# PCB_V7.net
KiCad netlist of a schematic drawn in EAGLE
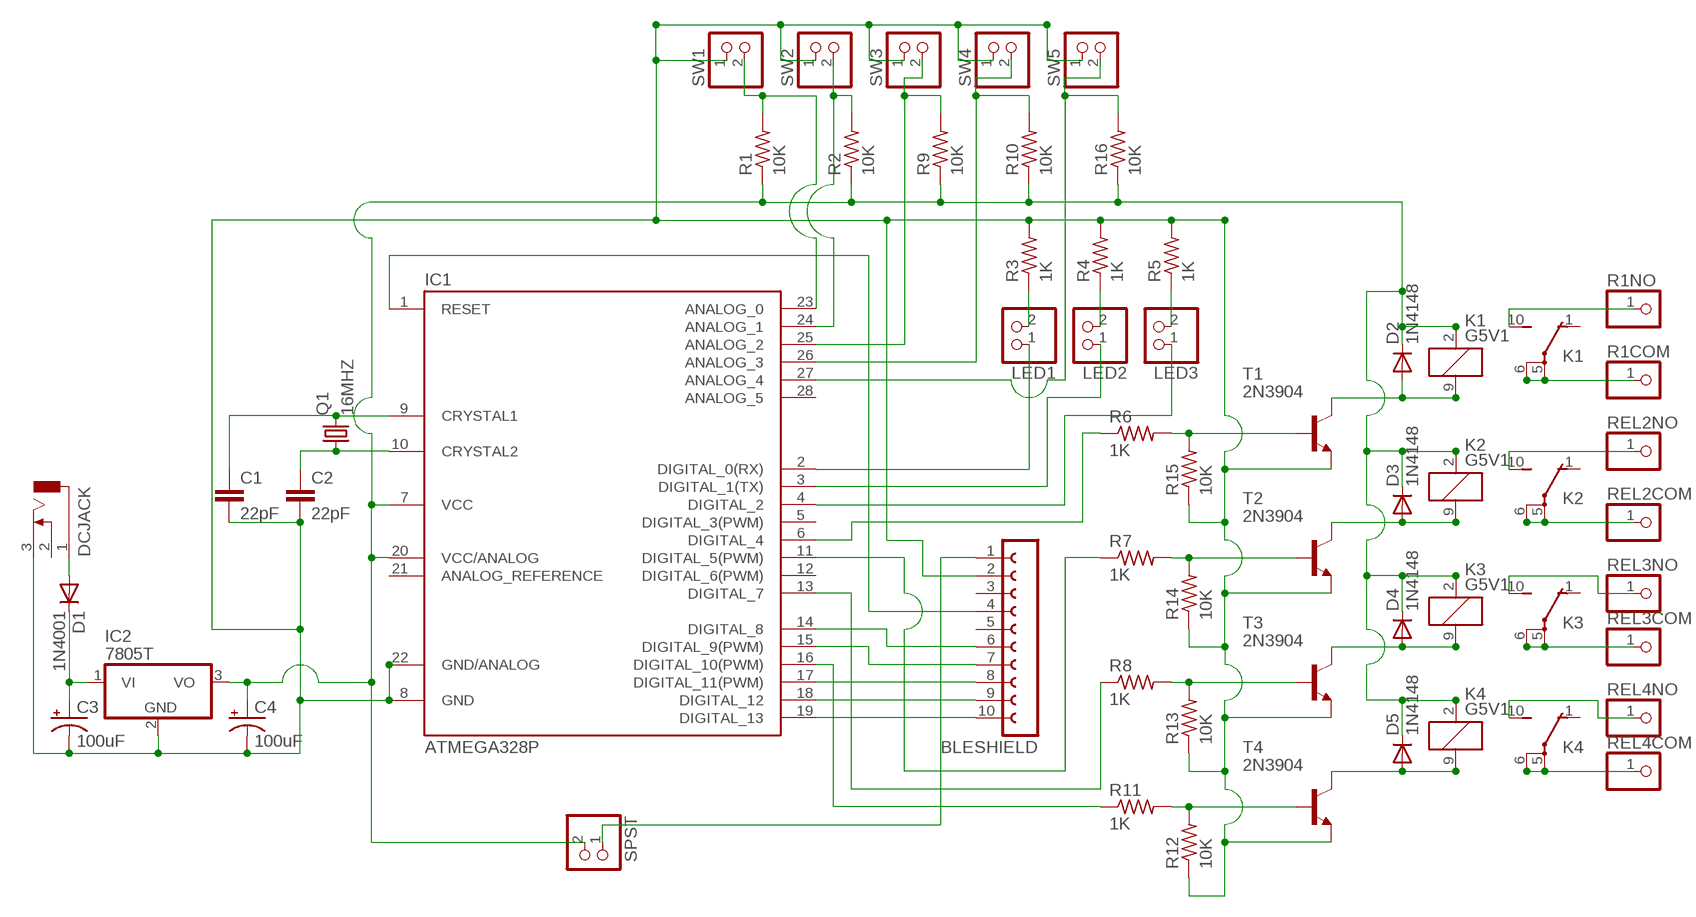
[diagram p0: schematic, sheet 1]

(export (version "E")
  (design (tool "Eeschema 10.0.6"))
  (components
    (comp (ref "BLESHIELD")
      (value "FE10-1")
      (footprint "eagle-import:FE10")
      (libsource (lib "eagle-import") (part "FE10-1"))
    )
    (comp (ref "C1")
      (value "22pF")
      (footprint "eagle-import:C025-030X050")
      (libsource (lib "eagle-import") (part "C-EU025-030X050"))
    )
    (comp (ref "C2")
      (value "22pF")
      (footprint "eagle-import:C025-030X050")
      (libsource (lib "eagle-import") (part "C-EU025-030X050"))
    )
    (comp (ref "C3")
      (value "100uF")
      (footprint "eagle-import:E2,5-6")
      (libsource (lib "eagle-import") (part "CPOL-USE2.5-6"))
    )
    (comp (ref "C4")
      (value "100uF")
      (footprint "eagle-import:E2,5-6")
      (libsource (lib "eagle-import") (part "CPOL-USE2.5-6"))
    )
    (comp (ref "D1")
      (value "1N4001")
      (footprint "eagle-import:DO41-10")
      (libsource (lib "eagle-import") (part "1N4004"))
    )
    (comp (ref "D2")
      (value "1N4148")
      (footprint "eagle-import:DO35-7")
      (libsource (lib "eagle-import") (part "1N4148DO35-7"))
    )
    (comp (ref "D3")
      (value "1N4148")
      (footprint "eagle-import:DO35-7")
      (libsource (lib "eagle-import") (part "1N4148DO35-7"))
    )
    (comp (ref "D4")
      (value "1N4148")
      (footprint "eagle-import:DO35-7")
      (libsource (lib "eagle-import") (part "1N4148DO35-7"))
    )
    (comp (ref "D5")
      (value "1N4148")
      (footprint "eagle-import:DO35-7")
      (libsource (lib "eagle-import") (part "1N4148DO35-7"))
    )
    (comp (ref "DCJACK")
      (value "DCJ0202")
      (footprint "eagle-import:DCJ0202")
      (libsource (lib "eagle-import") (part "DCJ0202"))
    )
    (comp (ref "IC1")
      (value "ATMEGA328P")
      (footprint "eagle-import:DIL28-3")
      (libsource (lib "eagle-import") (part "ATMEGA168-PU"))
    )
    (comp (ref "IC2")
      (value "7805T")
      (footprint "eagle-import:TO220H")
      (libsource (lib "eagle-import") (part "78T05"))
    )
    (comp (ref "K1")
      (value "G5V1")
      (footprint "eagle-import:G5V1")
      (fields (field (name "MPN") "G5V-1-DC24"))
      (libsource (lib "eagle-import") (part "G5V1"))
    )
    (comp (ref "K2")
      (value "G5V1")
      (footprint "eagle-import:G5V1")
      (fields (field (name "MPN") "G5V-1-DC24"))
      (libsource (lib "eagle-import") (part "G5V1"))
    )
    (comp (ref "K3")
      (value "G5V1")
      (footprint "eagle-import:G5V1")
      (fields (field (name "MPN") "G5V-1-DC24"))
      (libsource (lib "eagle-import") (part "G5V1"))
    )
    (comp (ref "K4")
      (value "G5V1")
      (footprint "eagle-import:G5V1")
      (fields (field (name "MPN") "G5V-1-DC24"))
      (libsource (lib "eagle-import") (part "G5V1"))
    )
    (comp (ref "LED1")
      (value "PINHD-1X2")
      (footprint "eagle-import:1X02")
      (libsource (lib "eagle-import") (part "PINHD-1X2"))
    )
    (comp (ref "LED2")
      (value "PINHD-1X2")
      (footprint "eagle-import:1X02")
      (libsource (lib "eagle-import") (part "PINHD-1X2"))
    )
    (comp (ref "LED3")
      (value "PINHD-1X2")
      (footprint "eagle-import:1X02")
      (libsource (lib "eagle-import") (part "PINHD-1X2"))
    )
    (comp (ref "Q1")
      (value "16MHZ")
      (footprint "eagle-import:HC49_S")
      (libsource (lib "eagle-import") (part "CRYSTALHC49S"))
    )
    (comp (ref "R1")
      (value "10K")
      (footprint "eagle-import:0204_5")
      (libsource (lib "eagle-import") (part "R-US_0204/5"))
    )
    (comp (ref "R1COM")
      (value "PINHD-1X1")
      (footprint "eagle-import:1X01")
      (libsource (lib "eagle-import") (part "PINHD-1X1"))
    )
    (comp (ref "R1NO")
      (value "PINHD-1X1")
      (footprint "eagle-import:1X01")
      (libsource (lib "eagle-import") (part "PINHD-1X1"))
    )
    (comp (ref "R2")
      (value "10K")
      (footprint "eagle-import:0204_5")
      (libsource (lib "eagle-import") (part "R-US_0204/5"))
    )
    (comp (ref "R3")
      (value "1K")
      (footprint "eagle-import:0204_5")
      (libsource (lib "eagle-import") (part "R-US_0204/5"))
    )
    (comp (ref "R4")
      (value "1K")
      (footprint "eagle-import:0204_5")
      (libsource (lib "eagle-import") (part "R-US_0204/5"))
    )
    (comp (ref "R5")
      (value "1K")
      (footprint "eagle-import:0204_5")
      (libsource (lib "eagle-import") (part "R-US_0204/5"))
    )
    (comp (ref "R6")
      (value "1K")
      (footprint "eagle-import:0204_5")
      (libsource (lib "eagle-import") (part "R-US_0204/5"))
    )
    (comp (ref "R7")
      (value "1K")
      (footprint "eagle-import:0204_5")
      (libsource (lib "eagle-import") (part "R-US_0204/5"))
    )
    (comp (ref "R8")
      (value "1K")
      (footprint "eagle-import:0204_5")
      (libsource (lib "eagle-import") (part "R-US_0204/5"))
    )
    (comp (ref "R9")
      (value "10K")
      (footprint "eagle-import:0204_5")
      (libsource (lib "eagle-import") (part "R-US_0204/5"))
    )
    (comp (ref "R10")
      (value "10K")
      (footprint "eagle-import:0204_5")
      (libsource (lib "eagle-import") (part "R-US_0204/5"))
    )
    (comp (ref "R11")
      (value "1K")
      (footprint "eagle-import:0204_5")
      (libsource (lib "eagle-import") (part "R-US_0204/5"))
    )
    (comp (ref "R12")
      (value "10K")
      (footprint "eagle-import:0204_5")
      (libsource (lib "eagle-import") (part "R-US_0204/5"))
    )
    (comp (ref "R13")
      (value "10K")
      (footprint "eagle-import:0204_5")
      (libsource (lib "eagle-import") (part "R-US_0204/5"))
    )
    (comp (ref "R14")
      (value "10K")
      (footprint "eagle-import:0204_5")
      (libsource (lib "eagle-import") (part "R-US_0204/5"))
    )
    (comp (ref "R15")
      (value "10K")
      (footprint "eagle-import:0204_5")
      (libsource (lib "eagle-import") (part "R-US_0204/5"))
    )
    (comp (ref "R16")
      (value "10K")
      (footprint "eagle-import:0204_5")
      (libsource (lib "eagle-import") (part "R-US_0204/5"))
    )
    (comp (ref "REL2COM")
      (value "PINHD-1X1")
      (footprint "eagle-import:1X01")
      (libsource (lib "eagle-import") (part "PINHD-1X1"))
    )
    (comp (ref "REL2NO")
      (value "PINHD-1X1")
      (footprint "eagle-import:1X01")
      (libsource (lib "eagle-import") (part "PINHD-1X1"))
    )
    (comp (ref "REL3COM")
      (value "PINHD-1X1")
      (footprint "eagle-import:1X01")
      (libsource (lib "eagle-import") (part "PINHD-1X1"))
    )
    (comp (ref "REL3NO")
      (value "PINHD-1X1")
      (footprint "eagle-import:1X01")
      (libsource (lib "eagle-import") (part "PINHD-1X1"))
    )
    (comp (ref "REL4COM")
      (value "PINHD-1X1")
      (footprint "eagle-import:1X01")
      (libsource (lib "eagle-import") (part "PINHD-1X1"))
    )
    (comp (ref "REL4NO")
      (value "PINHD-1X1")
      (footprint "eagle-import:1X01")
      (libsource (lib "eagle-import") (part "PINHD-1X1"))
    )
    (comp (ref "SPST")
      (value "PINHD-1X2")
      (footprint "eagle-import:1X02")
      (libsource (lib "eagle-import") (part "PINHD-1X2"))
    )
    (comp (ref "SW1")
      (value "PINHD-1X2")
      (footprint "eagle-import:1X02")
      (libsource (lib "eagle-import") (part "PINHD-1X2"))
    )
    (comp (ref "SW2")
      (value "PINHD-1X2")
      (footprint "eagle-import:1X02")
      (libsource (lib "eagle-import") (part "PINHD-1X2"))
    )
    (comp (ref "SW3")
      (value "PINHD-1X2")
      (footprint "eagle-import:1X02")
      (libsource (lib "eagle-import") (part "PINHD-1X2"))
    )
    (comp (ref "SW4")
      (value "PINHD-1X2")
      (footprint "eagle-import:1X02")
      (libsource (lib "eagle-import") (part "PINHD-1X2"))
    )
    (comp (ref "SW5")
      (value "PINHD-1X2")
      (footprint "eagle-import:1X02")
      (libsource (lib "eagle-import") (part "PINHD-1X2"))
    )
    (comp (ref "T1")
      (value "2N3904")
      (footprint "eagle-import:TO92")
      (libsource (lib "eagle-import") (part "2N3904"))
    )
    (comp (ref "T2")
      (value "2N3904")
      (footprint "eagle-import:TO92")
      (libsource (lib "eagle-import") (part "2N3904"))
    )
    (comp (ref "T3")
      (value "2N3904")
      (footprint "eagle-import:TO92")
      (libsource (lib "eagle-import") (part "2N3904"))
    )
    (comp (ref "T4")
      (value "2N3904")
      (footprint "eagle-import:TO92")
      (libsource (lib "eagle-import") (part "2N3904"))
    )
  )
  (nets
    (net (code "1") (name "Net-(BLESHIELD-Pad1)") (class "Default")
      (node (ref "BLESHIELD") (pin "1") (pinfunction "1_1") (pintype "passive"))
      (node (ref "SPST") (pin "1") (pinfunction "1_1") (pintype "passive"))
    )
    (net (code "2") (name "Net-(D1-PadA)") (class "Default")
      (node (ref "D1") (pin "A") (pinfunction "A_A") (pintype "passive"))
      (node (ref "DCJACK") (pin "1") (pinfunction "1_1") (pintype "passive"))
    )
    (net (code "3") (name "Net-(IC1-ANALOG_0)") (class "Default")
      (node (ref "IC1") (pin "23") (pinfunction "ANALOG_0_23") (pintype "bidirectional"))
      (node (ref "R1") (pin "2") (pinfunction "2_2") (pintype "passive"))
      (node (ref "SW1") (pin "2") (pinfunction "2_2") (pintype "passive"))
    )
    (net (code "4") (name "Net-(IC1-ANALOG_1)") (class "Default")
      (node (ref "IC1") (pin "24") (pinfunction "ANALOG_1_24") (pintype "bidirectional"))
      (node (ref "R2") (pin "2") (pinfunction "2_2") (pintype "passive"))
      (node (ref "SW2") (pin "2") (pinfunction "2_2") (pintype "passive"))
    )
    (net (code "5") (name "Net-(IC1-ANALOG_2)") (class "Default")
      (node (ref "IC1") (pin "25") (pinfunction "ANALOG_2_25") (pintype "bidirectional"))
      (node (ref "R9") (pin "2") (pinfunction "2_2") (pintype "passive"))
      (node (ref "SW3") (pin "2") (pinfunction "2_2") (pintype "passive"))
    )
    (net (code "6") (name "Net-(IC1-ANALOG_3)") (class "Default")
      (node (ref "IC1") (pin "26") (pinfunction "ANALOG_3_26") (pintype "bidirectional"))
      (node (ref "R10") (pin "2") (pinfunction "2_2") (pintype "passive"))
      (node (ref "SW4") (pin "2") (pinfunction "2_2") (pintype "passive"))
    )
    (net (code "7") (name "Net-(IC1-ANALOG_4)") (class "Default")
      (node (ref "IC1") (pin "27") (pinfunction "ANALOG_4_27") (pintype "bidirectional"))
      (node (ref "R16") (pin "2") (pinfunction "2_2") (pintype "passive"))
      (node (ref "SW5") (pin "2") (pinfunction "2_2") (pintype "passive"))
    )
    (net (code "8") (name "Net-(IC1-CRYSTAL1)") (class "Default")
      (node (ref "C1") (pin "1") (pinfunction "1_1") (pintype "passive"))
      (node (ref "IC1") (pin "9") (pinfunction "CRYSTAL1_9") (pintype "bidirectional"))
      (node (ref "Q1") (pin "2") (pinfunction "2_2") (pintype "passive"))
    )
    (net (code "9") (name "Net-(IC1-CRYSTAL2)") (class "Default")
      (node (ref "C2") (pin "1") (pinfunction "1_1") (pintype "passive"))
      (node (ref "IC1") (pin "10") (pinfunction "CRYSTAL2_10") (pintype "bidirectional"))
      (node (ref "Q1") (pin "1") (pinfunction "1_1") (pintype "passive"))
    )
    (net (code "10") (name "Net-(IC1-DIGITAL_0(RX))") (class "Default")
      (node (ref "IC1") (pin "2") (pinfunction "DIGITAL_0(RX)_2") (pintype "bidirectional"))
      (node (ref "LED1") (pin "1") (pinfunction "1_1") (pintype "passive"))
    )
    (net (code "11") (name "Net-(IC1-DIGITAL_1(TX))") (class "Default")
      (node (ref "IC1") (pin "3") (pinfunction "DIGITAL_1(TX)_3") (pintype "bidirectional"))
      (node (ref "LED2") (pin "1") (pinfunction "1_1") (pintype "passive"))
    )
    (net (code "12") (name "Net-(IC1-DIGITAL_2)") (class "Default")
      (node (ref "IC1") (pin "4") (pinfunction "DIGITAL_2_4") (pintype "bidirectional"))
      (node (ref "LED3") (pin "1") (pinfunction "1_1") (pintype "passive"))
    )
    (net (code "13") (name "Net-(IC1-DIGITAL_4)") (class "Default")
      (node (ref "IC1") (pin "6") (pinfunction "DIGITAL_4_6") (pintype "bidirectional"))
      (node (ref "R6") (pin "1") (pinfunction "1_1") (pintype "passive"))
    )
    (net (code "14") (name "Net-(IC1-DIGITAL_5(PWM))") (class "Default")
      (node (ref "IC1") (pin "11") (pinfunction "DIGITAL_5(PWM)_11") (pintype "bidirectional"))
      (node (ref "R7") (pin "1") (pinfunction "1_1") (pintype "passive"))
    )
    (net (code "15") (name "Net-(IC1-DIGITAL_7)") (class "Default")
      (node (ref "IC1") (pin "13") (pinfunction "DIGITAL_7_13") (pintype "bidirectional"))
      (node (ref "R8") (pin "1") (pinfunction "1_1") (pintype "passive"))
    )
    (net (code "16") (name "Net-(IC1-DIGITAL_8)") (class "Default")
      (node (ref "BLESHIELD") (pin "6") (pinfunction "6_6") (pintype "passive"))
      (node (ref "IC1") (pin "14") (pinfunction "DIGITAL_8_14") (pintype "bidirectional"))
    )
    (net (code "17") (name "Net-(IC1-DIGITAL_9(PWM))") (class "Default")
      (node (ref "BLESHIELD") (pin "7") (pinfunction "7_7") (pintype "passive"))
      (node (ref "IC1") (pin "15") (pinfunction "DIGITAL_9(PWM)_15") (pintype "bidirectional"))
    )
    (net (code "18") (name "Net-(IC1-DIGITAL_10(PWM))") (class "Default")
      (node (ref "IC1") (pin "16") (pinfunction "DIGITAL_10(PWM)_16") (pintype "bidirectional"))
      (node (ref "R11") (pin "1") (pinfunction "1_1") (pintype "passive"))
    )
    (net (code "19") (name "Net-(IC1-DIGITAL_11(PWM))") (class "Default")
      (node (ref "BLESHIELD") (pin "8") (pinfunction "8_8") (pintype "passive"))
      (node (ref "IC1") (pin "17") (pinfunction "DIGITAL_11(PWM)_17") (pintype "bidirectional"))
    )
    (net (code "20") (name "Net-(IC1-DIGITAL_12)") (class "Default")
      (node (ref "BLESHIELD") (pin "9") (pinfunction "9_9") (pintype "passive"))
      (node (ref "IC1") (pin "18") (pinfunction "DIGITAL_12_18") (pintype "bidirectional"))
    )
    (net (code "21") (name "Net-(IC1-DIGITAL_13)") (class "Default")
      (node (ref "BLESHIELD") (pin "10") (pinfunction "10_10") (pintype "passive"))
      (node (ref "IC1") (pin "19") (pinfunction "DIGITAL_13_19") (pintype "bidirectional"))
    )
    (net (code "22") (name "Net-(IC1-GND)") (class "Default")
      (node (ref "BLESHIELD") (pin "2") (pinfunction "2_2") (pintype "passive"))
      (node (ref "C1") (pin "2") (pinfunction "2_2") (pintype "passive"))
      (node (ref "C2") (pin "2") (pinfunction "2_2") (pintype "passive"))
      (node (ref "C3") (pin "-") (pinfunction "-_-") (pintype "passive"))
      (node (ref "C4") (pin "-") (pinfunction "-_-") (pintype "passive"))
      (node (ref "DCJACK") (pin "3") (pinfunction "3_3") (pintype "passive"))
      (node (ref "IC1") (pin "22") (pinfunction "GND/ANALOG_22") (pintype "power_in"))
      (node (ref "IC1") (pin "8") (pinfunction "GND_8") (pintype "power_in"))
      (node (ref "IC2") (pin "2") (pinfunction "GND_2") (pintype "passive"))
      (node (ref "R12") (pin "1") (pinfunction "1_1") (pintype "passive"))
      (node (ref "R13") (pin "1") (pinfunction "1_1") (pintype "passive"))
      (node (ref "R14") (pin "1") (pinfunction "1_1") (pintype "passive"))
      (node (ref "R15") (pin "1") (pinfunction "1_1") (pintype "passive"))
      (node (ref "R3") (pin "2") (pinfunction "2_2") (pintype "passive"))
      (node (ref "R4") (pin "2") (pinfunction "2_2") (pintype "passive"))
      (node (ref "R5") (pin "2") (pinfunction "2_2") (pintype "passive"))
      (node (ref "SW1") (pin "1") (pinfunction "1_1") (pintype "passive"))
      (node (ref "SW2") (pin "1") (pinfunction "1_1") (pintype "passive"))
      (node (ref "SW3") (pin "1") (pinfunction "1_1") (pintype "passive"))
      (node (ref "SW4") (pin "1") (pinfunction "1_1") (pintype "passive"))
      (node (ref "SW5") (pin "1") (pinfunction "1_1") (pintype "passive"))
      (node (ref "T1") (pin "3") (pinfunction "E_3") (pintype "passive"))
      (node (ref "T2") (pin "3") (pinfunction "E_3") (pintype "passive"))
      (node (ref "T3") (pin "3") (pinfunction "E_3") (pintype "passive"))
      (node (ref "T4") (pin "3") (pinfunction "E_3") (pintype "passive"))
    )
    (net (code "23") (name "Net-(IC1-RESET)") (class "Default")
      (node (ref "BLESHIELD") (pin "4") (pinfunction "4_4") (pintype "passive"))
      (node (ref "IC1") (pin "1") (pinfunction "RESET_1") (pintype "bidirectional"))
    )
    (net (code "24") (name "Net-(IC1-VCC)") (class "Default")
      (node (ref "C4") (pin "+") (pinfunction "+_+") (pintype "passive"))
      (node (ref "D2") (pin "C") (pinfunction "C_C") (pintype "passive"))
      (node (ref "D3") (pin "C") (pinfunction "C_C") (pintype "passive"))
      (node (ref "D4") (pin "C") (pinfunction "C_C") (pintype "passive"))
      (node (ref "D5") (pin "C") (pinfunction "C_C") (pintype "passive"))
      (node (ref "IC1") (pin "20") (pinfunction "VCC/ANALOG_20") (pintype "passive"))
      (node (ref "IC1") (pin "7") (pinfunction "VCC_7") (pintype "power_in"))
      (node (ref "IC2") (pin "3") (pinfunction "VO_3") (pintype "passive"))
      (node (ref "K1") (pin "2") (pinfunction "1_2") (pintype "passive"))
      (node (ref "K2") (pin "2") (pinfunction "1_2") (pintype "passive"))
      (node (ref "K3") (pin "2") (pinfunction "1_2") (pintype "passive"))
      (node (ref "K4") (pin "2") (pinfunction "1_2") (pintype "passive"))
      (node (ref "R1") (pin "1") (pinfunction "1_1") (pintype "passive"))
      (node (ref "R10") (pin "1") (pinfunction "1_1") (pintype "passive"))
      (node (ref "R16") (pin "1") (pinfunction "1_1") (pintype "passive"))
      (node (ref "R2") (pin "1") (pinfunction "1_1") (pintype "passive"))
      (node (ref "R9") (pin "1") (pinfunction "1_1") (pintype "passive"))
      (node (ref "SPST") (pin "2") (pinfunction "2_2") (pintype "passive"))
    )
    (net (code "25") (name "Net-(IC2-VI)") (class "Default")
      (node (ref "C3") (pin "+") (pinfunction "+_+") (pintype "passive"))
      (node (ref "D1") (pin "C") (pinfunction "C_C") (pintype "passive"))
      (node (ref "IC2") (pin "1") (pinfunction "VI_1") (pintype "input"))
    )
    (net (code "26") (name "Net-(K1A-2)") (class "Default")
      (node (ref "D2") (pin "A") (pinfunction "A_A") (pintype "passive"))
      (node (ref "K1") (pin "9") (pinfunction "2_9") (pintype "passive"))
      (node (ref "T1") (pin "1") (pinfunction "C_1") (pintype "passive"))
    )
    (net (code "27") (name "Net-(K1B-P-Pad5)") (class "Default")
      (node (ref "K1") (pin "5") (pinfunction "P_5") (pintype "passive"))
      (node (ref "K1") (pin "6") (pinfunction "P_6") (pintype "passive"))
      (node (ref "R1COM") (pin "1") (pinfunction "1_1") (pintype "passive"))
    )
    (net (code "28") (name "Net-(K1B-S)") (class "Default")
      (node (ref "K1") (pin "10") (pinfunction "S_10") (pintype "passive"))
      (node (ref "R1NO") (pin "1") (pinfunction "1_1") (pintype "passive"))
    )
    (net (code "29") (name "Net-(K2A-2)") (class "Default")
      (node (ref "D3") (pin "A") (pinfunction "A_A") (pintype "passive"))
      (node (ref "K2") (pin "9") (pinfunction "2_9") (pintype "passive"))
      (node (ref "T2") (pin "1") (pinfunction "C_1") (pintype "passive"))
    )
    (net (code "30") (name "Net-(K2B-P-Pad5)") (class "Default")
      (node (ref "K2") (pin "5") (pinfunction "P_5") (pintype "passive"))
      (node (ref "K2") (pin "6") (pinfunction "P_6") (pintype "passive"))
      (node (ref "REL2COM") (pin "1") (pinfunction "1_1") (pintype "passive"))
    )
    (net (code "31") (name "Net-(K2B-S)") (class "Default")
      (node (ref "K2") (pin "10") (pinfunction "S_10") (pintype "passive"))
      (node (ref "REL2NO") (pin "1") (pinfunction "1_1") (pintype "passive"))
    )
    (net (code "32") (name "Net-(K3A-2)") (class "Default")
      (node (ref "D4") (pin "A") (pinfunction "A_A") (pintype "passive"))
      (node (ref "K3") (pin "9") (pinfunction "2_9") (pintype "passive"))
      (node (ref "T3") (pin "1") (pinfunction "C_1") (pintype "passive"))
    )
    (net (code "33") (name "Net-(K3B-P-Pad5)") (class "Default")
      (node (ref "K3") (pin "5") (pinfunction "P_5") (pintype "passive"))
      (node (ref "K3") (pin "6") (pinfunction "P_6") (pintype "passive"))
      (node (ref "REL3COM") (pin "1") (pinfunction "1_1") (pintype "passive"))
    )
    (net (code "34") (name "Net-(K3B-S)") (class "Default")
      (node (ref "K3") (pin "10") (pinfunction "S_10") (pintype "passive"))
      (node (ref "REL3NO") (pin "1") (pinfunction "1_1") (pintype "passive"))
    )
    (net (code "35") (name "Net-(K4A-2)") (class "Default")
      (node (ref "D5") (pin "A") (pinfunction "A_A") (pintype "passive"))
      (node (ref "K4") (pin "9") (pinfunction "2_9") (pintype "passive"))
      (node (ref "T4") (pin "1") (pinfunction "C_1") (pintype "passive"))
    )
    (net (code "36") (name "Net-(K4B-P-Pad5)") (class "Default")
      (node (ref "K4") (pin "5") (pinfunction "P_5") (pintype "passive"))
      (node (ref "K4") (pin "6") (pinfunction "P_6") (pintype "passive"))
      (node (ref "REL4COM") (pin "1") (pinfunction "1_1") (pintype "passive"))
    )
    (net (code "37") (name "Net-(K4B-S)") (class "Default")
      (node (ref "K4") (pin "10") (pinfunction "S_10") (pintype "passive"))
      (node (ref "REL4NO") (pin "1") (pinfunction "1_1") (pintype "passive"))
    )
    (net (code "38") (name "Net-(LED1-Pad2)") (class "Default")
      (node (ref "LED1") (pin "2") (pinfunction "2_2") (pintype "passive"))
      (node (ref "R3") (pin "1") (pinfunction "1_1") (pintype "passive"))
    )
    (net (code "39") (name "Net-(LED2-Pad2)") (class "Default")
      (node (ref "LED2") (pin "2") (pinfunction "2_2") (pintype "passive"))
      (node (ref "R4") (pin "1") (pinfunction "1_1") (pintype "passive"))
    )
    (net (code "40") (name "Net-(LED3-Pad2)") (class "Default")
      (node (ref "LED3") (pin "2") (pinfunction "2_2") (pintype "passive"))
      (node (ref "R5") (pin "1") (pinfunction "1_1") (pintype "passive"))
    )
    (net (code "41") (name "Net-(T1-B)") (class "Default")
      (node (ref "R15") (pin "2") (pinfunction "2_2") (pintype "passive"))
      (node (ref "R6") (pin "2") (pinfunction "2_2") (pintype "passive"))
      (node (ref "T1") (pin "2") (pinfunction "B_2") (pintype "passive"))
    )
    (net (code "42") (name "Net-(T2-B)") (class "Default")
      (node (ref "R14") (pin "2") (pinfunction "2_2") (pintype "passive"))
      (node (ref "R7") (pin "2") (pinfunction "2_2") (pintype "passive"))
      (node (ref "T2") (pin "2") (pinfunction "B_2") (pintype "passive"))
    )
    (net (code "43") (name "Net-(T3-B)") (class "Default")
      (node (ref "R13") (pin "2") (pinfunction "2_2") (pintype "passive"))
      (node (ref "R8") (pin "2") (pinfunction "2_2") (pintype "passive"))
      (node (ref "T3") (pin "2") (pinfunction "B_2") (pintype "passive"))
    )
    (net (code "44") (name "Net-(T4-B)") (class "Default")
      (node (ref "R11") (pin "2") (pinfunction "2_2") (pintype "passive"))
      (node (ref "R12") (pin "2") (pinfunction "2_2") (pintype "passive"))
      (node (ref "T4") (pin "2") (pinfunction "B_2") (pintype "passive"))
    )
    (net (code "45") (name "unconnected-(BLESHIELD-Pad3)") (class "Default")
      (node (ref "BLESHIELD") (pin "3") (pinfunction "3_3") (pintype "passive"))
    )
    (net (code "46") (name "unconnected-(BLESHIELD-Pad5)") (class "Default")
      (node (ref "BLESHIELD") (pin "5") (pinfunction "5_5") (pintype "passive"))
    )
    (net (code "47") (name "unconnected-(DCJACK-Pad2)") (class "Default")
      (node (ref "DCJACK") (pin "2") (pinfunction "2_2") (pintype "passive"))
    )
    (net (code "48") (name "unconnected-(IC1-ANALOG_5-Pad28)") (class "Default")
      (node (ref "IC1") (pin "28") (pinfunction "ANALOG_5_28") (pintype "bidirectional"))
    )
    (net (code "49") (name "unconnected-(IC1-ANALOG_REFERENCE-Pad21)") (class "Default")
      (node (ref "IC1") (pin "21") (pinfunction "ANALOG_REFERENCE_21") (pintype "passive"))
    )
    (net (code "50") (name "unconnected-(IC1-DIGITAL_3(PWM)-Pad5)") (class "Default")
      (node (ref "IC1") (pin "5") (pinfunction "DIGITAL_3(PWM)_5") (pintype "bidirectional"))
    )
    (net (code "51") (name "unconnected-(IC1-DIGITAL_6(PWM)-Pad12)") (class "Default")
      (node (ref "IC1") (pin "12") (pinfunction "DIGITAL_6(PWM)_12") (pintype "bidirectional"))
    )
    (net (code "52") (name "unconnected-(K1B-O-Pad1)") (class "Default")
      (node (ref "K1") (pin "1") (pinfunction "O_1") (pintype "passive"))
    )
    (net (code "53") (name "unconnected-(K2B-O-Pad1)") (class "Default")
      (node (ref "K2") (pin "1") (pinfunction "O_1") (pintype "passive"))
    )
    (net (code "54") (name "unconnected-(K3B-O-Pad1)") (class "Default")
      (node (ref "K3") (pin "1") (pinfunction "O_1") (pintype "passive"))
    )
    (net (code "55") (name "unconnected-(K4B-O-Pad1)") (class "Default")
      (node (ref "K4") (pin "1") (pinfunction "O_1") (pintype "passive"))
    )
  )
)
